# EasyEDA_SCH_Display_2023-01-10.net
KiCad netlist of a schematic drawn in EasyEDA
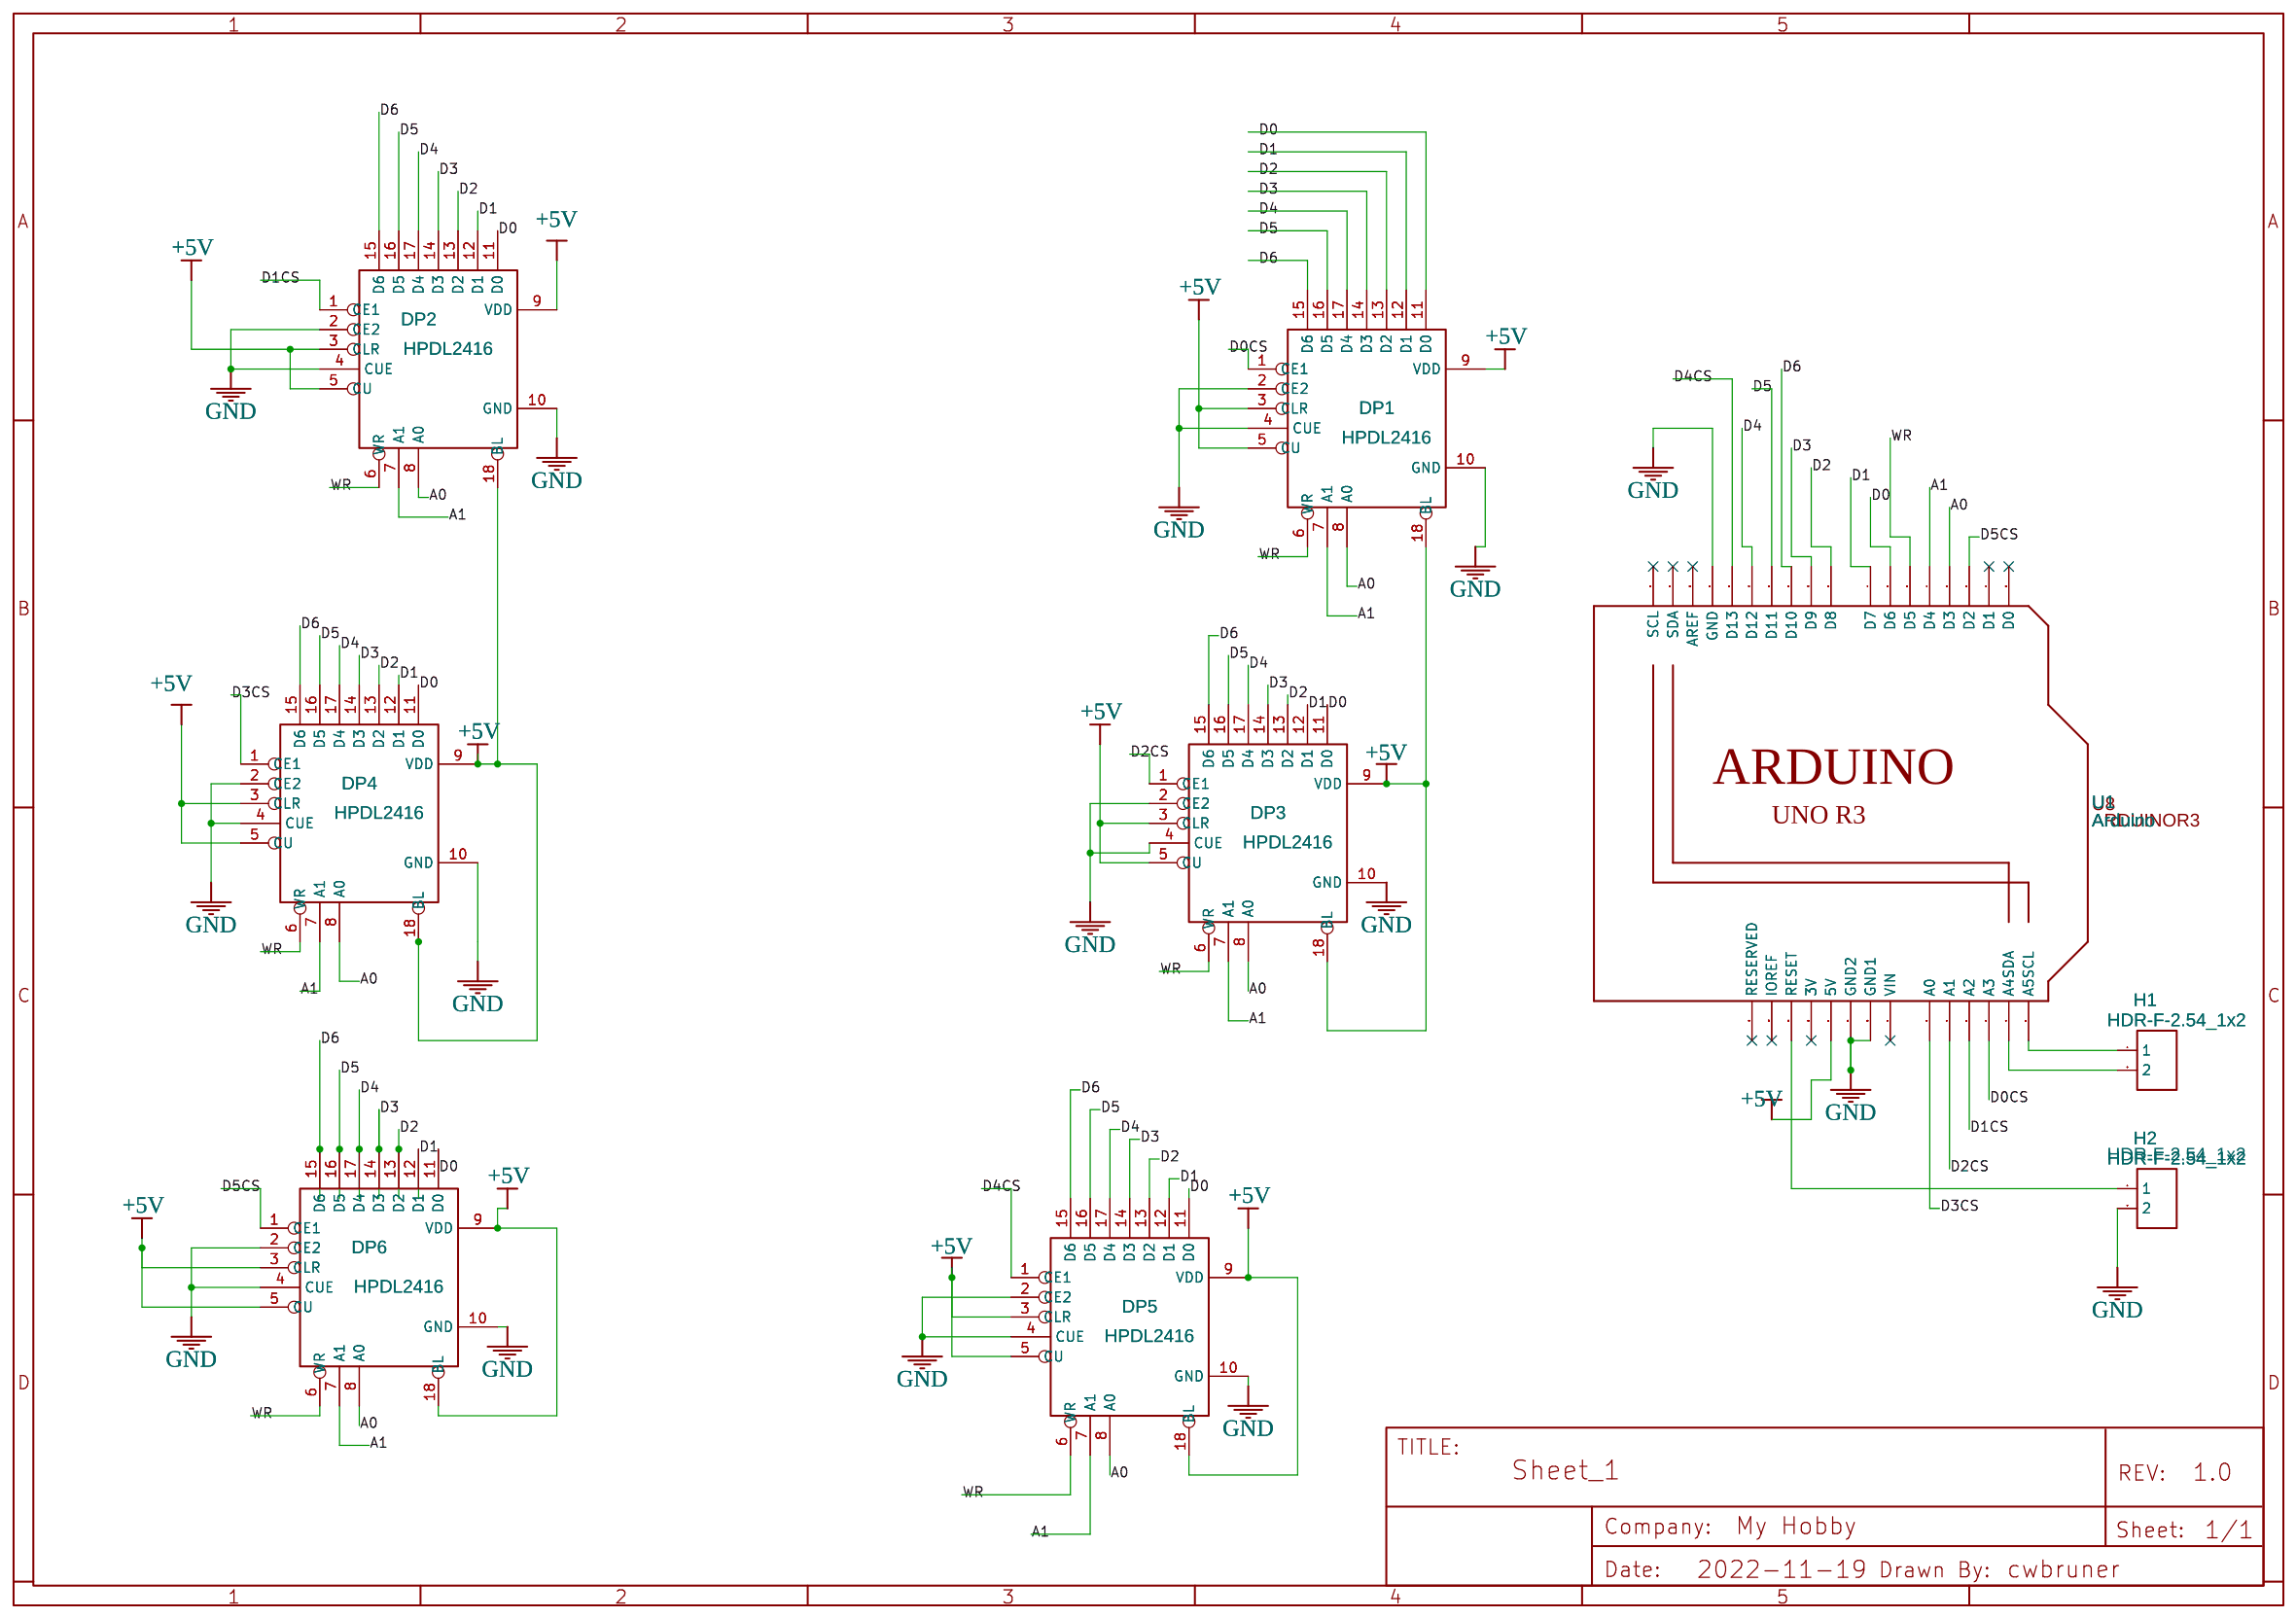
[diagram p0: schematic sheet]

(export (version "E")
  (design (tool "Eeschema 10.0.6"))
  (components
    (comp (ref "DP1")
      (value "HPDL2416")
      (fields (field (name "BOM_Supplier Part") "HPDL-2416"))
      (libsource (lib "") (part "HPDL2416"))
    )
    (comp (ref "DP2")
      (value "HPDL2416")
      (fields (field (name "BOM_Supplier Part") "HPDL-2416"))
      (libsource (lib "") (part "HPDL2416"))
    )
    (comp (ref "DP3")
      (value "HPDL2416")
      (fields (field (name "BOM_Supplier Part") "HPDL-2416"))
      (libsource (lib "") (part "HPDL2416"))
    )
    (comp (ref "DP4")
      (value "HPDL2416")
      (fields (field (name "BOM_Supplier Part") "HPDL-2416"))
      (libsource (lib "") (part "HPDL2416"))
    )
    (comp (ref "DP5")
      (value "HPDL2416")
      (fields (field (name "BOM_Supplier Part") "HPDL-2416"))
      (libsource (lib "") (part "HPDL2416"))
    )
    (comp (ref "DP6")
      (value "HPDL2416")
      (fields (field (name "BOM_Supplier Part") "HPDL-2416"))
      (libsource (lib "") (part "HPDL2416"))
    )
    (comp (ref "H1")
      (value "HDR-F-2.54_1x2")
      (fields (field (name "BOM_Supplier Part") "C49661"))
      (libsource (lib "") (part "HDR-F-2.54_1x2"))
    )
    (comp (ref "H2")
      (value "HDR-F-2.54_1x2")
      (fields (field (name "BOM_Supplier Part") "C49661"))
      (libsource (lib "") (part "HDR-F-2.54_1x2"))
    )
    (comp (ref "U1") (value "Arduino") (libsource (lib "") (part "Arduino")))
  )
  (nets
    (net (code "1") (name "+5V") (class "Default")
      (node (ref "DP1") (pin "18") (pinfunction "BL_18") (pintype "unspecified"))
      (node (ref "DP1") (pin "3") (pinfunction "CLR_3") (pintype "unspecified"))
      (node (ref "DP1") (pin "5") (pinfunction "CU_5") (pintype "unspecified"))
      (node (ref "DP1") (pin "9") (pinfunction "VDD_9") (pintype "unspecified"))
      (node (ref "DP2") (pin "18") (pinfunction "BL_18") (pintype "unspecified"))
      (node (ref "DP2") (pin "3") (pinfunction "CLR_3") (pintype "unspecified"))
      (node (ref "DP2") (pin "5") (pinfunction "CU_5") (pintype "unspecified"))
      (node (ref "DP2") (pin "9") (pinfunction "VDD_9") (pintype "unspecified"))
      (node (ref "DP3") (pin "18") (pinfunction "BL_18") (pintype "unspecified"))
      (node (ref "DP3") (pin "3") (pinfunction "CLR_3") (pintype "unspecified"))
      (node (ref "DP3") (pin "5") (pinfunction "CU_5") (pintype "unspecified"))
      (node (ref "DP3") (pin "9") (pinfunction "VDD_9") (pintype "unspecified"))
      (node (ref "DP4") (pin "18") (pinfunction "BL_18") (pintype "unspecified"))
      (node (ref "DP4") (pin "3") (pinfunction "CLR_3") (pintype "unspecified"))
      (node (ref "DP4") (pin "5") (pinfunction "CU_5") (pintype "unspecified"))
      (node (ref "DP4") (pin "9") (pinfunction "VDD_9") (pintype "unspecified"))
      (node (ref "DP5") (pin "18") (pinfunction "BL_18") (pintype "unspecified"))
      (node (ref "DP5") (pin "3") (pinfunction "CLR_3") (pintype "unspecified"))
      (node (ref "DP5") (pin "5") (pinfunction "CU_5") (pintype "unspecified"))
      (node (ref "DP5") (pin "9") (pinfunction "VDD_9") (pintype "unspecified"))
      (node (ref "DP6") (pin "18") (pinfunction "BL_18") (pintype "unspecified"))
      (node (ref "DP6") (pin "3") (pinfunction "CLR_3") (pintype "unspecified"))
      (node (ref "DP6") (pin "5") (pinfunction "CU_5") (pintype "unspecified"))
      (node (ref "DP6") (pin "9") (pinfunction "VDD_9") (pintype "unspecified"))
      (node (ref "U1") (pin "5V") (pinfunction "5V_5V") (pintype "passive"))
    )
    (net (code "2") (name "/A0") (class "Default")
      (node (ref "DP1") (pin "8") (pinfunction "A0_8") (pintype "unspecified"))
      (node (ref "DP2") (pin "8") (pinfunction "A0_8") (pintype "unspecified"))
      (node (ref "DP3") (pin "8") (pinfunction "A0_8") (pintype "unspecified"))
      (node (ref "DP4") (pin "8") (pinfunction "A0_8") (pintype "unspecified"))
      (node (ref "DP5") (pin "8") (pinfunction "A0_8") (pintype "unspecified"))
      (node (ref "DP6") (pin "8") (pinfunction "A0_8") (pintype "unspecified"))
      (node (ref "U1") (pin "3") (pinfunction "D3_3") (pintype "unspecified"))
    )
    (net (code "3") (name "/A1") (class "Default")
      (node (ref "DP1") (pin "7") (pinfunction "A1_7") (pintype "unspecified"))
      (node (ref "DP2") (pin "7") (pinfunction "A1_7") (pintype "unspecified"))
      (node (ref "DP3") (pin "7") (pinfunction "A1_7") (pintype "unspecified"))
      (node (ref "DP4") (pin "7") (pinfunction "A1_7") (pintype "unspecified"))
      (node (ref "DP5") (pin "7") (pinfunction "A1_7") (pintype "unspecified"))
      (node (ref "DP6") (pin "7") (pinfunction "A1_7") (pintype "unspecified"))
      (node (ref "U1") (pin "4") (pinfunction "D4_4") (pintype "unspecified"))
    )
    (net (code "4") (name "/D0") (class "Default")
      (node (ref "DP1") (pin "11") (pinfunction "D0_11") (pintype "unspecified"))
      (node (ref "DP2") (pin "11") (pinfunction "D0_11") (pintype "unspecified"))
      (node (ref "DP3") (pin "11") (pinfunction "D0_11") (pintype "unspecified"))
      (node (ref "DP4") (pin "11") (pinfunction "D0_11") (pintype "unspecified"))
      (node (ref "DP5") (pin "11") (pinfunction "D0_11") (pintype "unspecified"))
      (node (ref "DP6") (pin "11") (pinfunction "D0_11") (pintype "unspecified"))
      (node (ref "U1") (pin "6") (pinfunction "D6_6") (pintype "unspecified"))
    )
    (net (code "5") (name "/D0CS") (class "Default")
      (node (ref "DP1") (pin "1") (pinfunction "CE1_1") (pintype "unspecified"))
      (node (ref "U1") (pin "A3") (pinfunction "A3_A3") (pintype "unspecified"))
    )
    (net (code "6") (name "/D1") (class "Default")
      (node (ref "DP1") (pin "12") (pinfunction "D1_12") (pintype "unspecified"))
      (node (ref "DP2") (pin "12") (pinfunction "D1_12") (pintype "unspecified"))
      (node (ref "DP3") (pin "12") (pinfunction "D1_12") (pintype "unspecified"))
      (node (ref "DP4") (pin "12") (pinfunction "D1_12") (pintype "unspecified"))
      (node (ref "DP5") (pin "12") (pinfunction "D1_12") (pintype "unspecified"))
      (node (ref "DP6") (pin "12") (pinfunction "D1_12") (pintype "unspecified"))
      (node (ref "U1") (pin "7") (pinfunction "D7_7") (pintype "unspecified"))
    )
    (net (code "7") (name "/D1CS") (class "Default")
      (node (ref "DP2") (pin "1") (pinfunction "CE1_1") (pintype "unspecified"))
      (node (ref "U1") (pin "A2") (pinfunction "A2_A2") (pintype "unspecified"))
    )
    (net (code "8") (name "/D2") (class "Default")
      (node (ref "DP1") (pin "13") (pinfunction "D2_13") (pintype "unspecified"))
      (node (ref "DP2") (pin "13") (pinfunction "D2_13") (pintype "unspecified"))
      (node (ref "DP3") (pin "13") (pinfunction "D2_13") (pintype "unspecified"))
      (node (ref "DP4") (pin "13") (pinfunction "D2_13") (pintype "unspecified"))
      (node (ref "DP5") (pin "13") (pinfunction "D2_13") (pintype "unspecified"))
      (node (ref "DP6") (pin "13") (pinfunction "D2_13") (pintype "unspecified"))
      (node (ref "U1") (pin "8") (pinfunction "D8_8") (pintype "unspecified"))
    )
    (net (code "9") (name "/D2CS") (class "Default")
      (node (ref "DP3") (pin "1") (pinfunction "CE1_1") (pintype "unspecified"))
      (node (ref "U1") (pin "A1") (pinfunction "A1_A1") (pintype "unspecified"))
    )
    (net (code "10") (name "/D3") (class "Default")
      (node (ref "DP1") (pin "14") (pinfunction "D3_14") (pintype "unspecified"))
      (node (ref "DP2") (pin "14") (pinfunction "D3_14") (pintype "unspecified"))
      (node (ref "DP3") (pin "14") (pinfunction "D3_14") (pintype "unspecified"))
      (node (ref "DP4") (pin "14") (pinfunction "D3_14") (pintype "unspecified"))
      (node (ref "DP5") (pin "14") (pinfunction "D3_14") (pintype "unspecified"))
      (node (ref "DP6") (pin "14") (pinfunction "D3_14") (pintype "unspecified"))
      (node (ref "U1") (pin "9") (pinfunction "D9_9") (pintype "unspecified"))
    )
    (net (code "11") (name "/D3CS") (class "Default")
      (node (ref "DP4") (pin "1") (pinfunction "CE1_1") (pintype "unspecified"))
      (node (ref "U1") (pin "A0") (pinfunction "A0_A0") (pintype "unspecified"))
    )
    (net (code "12") (name "/D4") (class "Default")
      (node (ref "DP1") (pin "17") (pinfunction "D4_17") (pintype "unspecified"))
      (node (ref "DP2") (pin "17") (pinfunction "D4_17") (pintype "unspecified"))
      (node (ref "DP3") (pin "17") (pinfunction "D4_17") (pintype "unspecified"))
      (node (ref "DP4") (pin "17") (pinfunction "D4_17") (pintype "unspecified"))
      (node (ref "DP5") (pin "17") (pinfunction "D4_17") (pintype "unspecified"))
      (node (ref "DP6") (pin "17") (pinfunction "D4_17") (pintype "unspecified"))
      (node (ref "U1") (pin "12") (pinfunction "D12_12") (pintype "unspecified"))
    )
    (net (code "13") (name "/D4CS") (class "Default")
      (node (ref "DP5") (pin "1") (pinfunction "CE1_1") (pintype "unspecified"))
      (node (ref "U1") (pin "13") (pinfunction "D13_13") (pintype "unspecified"))
    )
    (net (code "14") (name "/D5") (class "Default")
      (node (ref "DP1") (pin "16") (pinfunction "D5_16") (pintype "unspecified"))
      (node (ref "DP2") (pin "16") (pinfunction "D5_16") (pintype "unspecified"))
      (node (ref "DP3") (pin "16") (pinfunction "D5_16") (pintype "unspecified"))
      (node (ref "DP4") (pin "16") (pinfunction "D5_16") (pintype "unspecified"))
      (node (ref "DP5") (pin "16") (pinfunction "D5_16") (pintype "unspecified"))
      (node (ref "DP6") (pin "16") (pinfunction "D5_16") (pintype "unspecified"))
      (node (ref "U1") (pin "11") (pinfunction "D11_11") (pintype "unspecified"))
    )
    (net (code "15") (name "/D5CS") (class "Default")
      (node (ref "DP6") (pin "1") (pinfunction "CE1_1") (pintype "unspecified"))
      (node (ref "U1") (pin "2") (pinfunction "D2_2") (pintype "unspecified"))
    )
    (net (code "16") (name "/D6") (class "Default")
      (node (ref "DP1") (pin "15") (pinfunction "D6_15") (pintype "unspecified"))
      (node (ref "DP2") (pin "15") (pinfunction "D6_15") (pintype "unspecified"))
      (node (ref "DP3") (pin "15") (pinfunction "D6_15") (pintype "unspecified"))
      (node (ref "DP4") (pin "15") (pinfunction "D6_15") (pintype "unspecified"))
      (node (ref "DP5") (pin "15") (pinfunction "D6_15") (pintype "unspecified"))
      (node (ref "DP6") (pin "15") (pinfunction "D6_15") (pintype "unspecified"))
      (node (ref "U1") (pin "10") (pinfunction "D10_10") (pintype "unspecified"))
    )
    (net (code "17") (name "/WR") (class "Default")
      (node (ref "DP1") (pin "6") (pinfunction "WR_6") (pintype "unspecified"))
      (node (ref "DP2") (pin "6") (pinfunction "WR_6") (pintype "unspecified"))
      (node (ref "DP3") (pin "6") (pinfunction "WR_6") (pintype "unspecified"))
      (node (ref "DP4") (pin "6") (pinfunction "WR_6") (pintype "unspecified"))
      (node (ref "DP5") (pin "6") (pinfunction "WR_6") (pintype "unspecified"))
      (node (ref "DP6") (pin "6") (pinfunction "WR_6") (pintype "unspecified"))
      (node (ref "U1") (pin "5") (pinfunction "D5_5") (pintype "unspecified"))
    )
    (net (code "18") (name "GND") (class "Default")
      (node (ref "DP1") (pin "10") (pinfunction "GND_10") (pintype "unspecified"))
      (node (ref "DP1") (pin "2") (pinfunction "CE2_2") (pintype "unspecified"))
      (node (ref "DP1") (pin "4") (pinfunction "CUE_4") (pintype "unspecified"))
      (node (ref "DP2") (pin "10") (pinfunction "GND_10") (pintype "unspecified"))
      (node (ref "DP2") (pin "2") (pinfunction "CE2_2") (pintype "unspecified"))
      (node (ref "DP2") (pin "4") (pinfunction "CUE_4") (pintype "unspecified"))
      (node (ref "DP3") (pin "10") (pinfunction "GND_10") (pintype "unspecified"))
      (node (ref "DP3") (pin "2") (pinfunction "CE2_2") (pintype "unspecified"))
      (node (ref "DP3") (pin "4") (pinfunction "CUE_4") (pintype "unspecified"))
      (node (ref "DP4") (pin "10") (pinfunction "GND_10") (pintype "unspecified"))
      (node (ref "DP4") (pin "2") (pinfunction "CE2_2") (pintype "unspecified"))
      (node (ref "DP4") (pin "4") (pinfunction "CUE_4") (pintype "unspecified"))
      (node (ref "DP5") (pin "10") (pinfunction "GND_10") (pintype "unspecified"))
      (node (ref "DP5") (pin "2") (pinfunction "CE2_2") (pintype "unspecified"))
      (node (ref "DP5") (pin "4") (pinfunction "CUE_4") (pintype "unspecified"))
      (node (ref "DP6") (pin "10") (pinfunction "GND_10") (pintype "unspecified"))
      (node (ref "DP6") (pin "2") (pinfunction "CE2_2") (pintype "unspecified"))
      (node (ref "DP6") (pin "4") (pinfunction "CUE_4") (pintype "unspecified"))
      (node (ref "H2") (pin "2") (pinfunction "2_2") (pintype "input"))
      (node (ref "U1") (pin "GND") (pinfunction "GND_GND") (pintype "passive"))
    )
    (net (code "19") (name "Net-(H2-Pad1)") (class "Default")
      (node (ref "H2") (pin "1") (pinfunction "1_1") (pintype "input"))
      (node (ref "U1") (pin "RESET") (pinfunction "RESET_RESET") (pintype "unspecified"))
    )
    (net (code "20") (name "Net-(U1-A4SDA)") (class "Default")
      (node (ref "H1") (pin "2") (pinfunction "2_2") (pintype "input"))
      (node (ref "U1") (pin "A4") (pinfunction "A4SDA_A4") (pintype "unspecified"))
    )
    (net (code "21") (name "Net-(U1-A5SCL)") (class "Default")
      (node (ref "H1") (pin "1") (pinfunction "1_1") (pintype "input"))
      (node (ref "U1") (pin "A5") (pinfunction "A5SCL_A5") (pintype "unspecified"))
    )
    (net (code "22") (name "unconnected-(U1-3V-Pad3.3V)") (class "Default")
      (node (ref "U1") (pin "3.3V") (pinfunction "3V_3.3V") (pintype "passive+no_connect"))
    )
    (net (code "23") (name "unconnected-(U1-D0-Pad0)") (class "Default")
      (node (ref "U1") (pin "0") (pinfunction "D0_0") (pintype "unspecified+no_connect"))
    )
    (net (code "24") (name "unconnected-(U1-D1-Pad1)") (class "Default")
      (node (ref "U1") (pin "1") (pinfunction "D1_1") (pintype "unspecified+no_connect"))
    )
    (net (code "25") (name "unconnected-(U1-IOREF-PadI{slash}OREF)") (class "Default")
      (node (ref "U1") (pin "I/OREF") (pinfunction "IOREF_I/OREF") (pintype "output+no_connect"))
    )
    (net (code "26") (name "unconnected-(U1-PadAREF)") (class "Default")
      (node (ref "U1") (pin "AREF") (pinfunction "AREF_AREF") (pintype "unspecified+no_connect"))
    )
    (net (code "27") (name "unconnected-(U1-PadSCL)") (class "Default")
      (node (ref "U1") (pin "SCL") (pinfunction "SCL_SCL") (pintype "unspecified+no_connect"))
    )
    (net (code "28") (name "unconnected-(U1-PadSDA)") (class "Default")
      (node (ref "U1") (pin "SDA") (pinfunction "SDA_SDA") (pintype "unspecified+no_connect"))
    )
    (net (code "29") (name "unconnected-(U1-PadVIN)") (class "Default")
      (node (ref "U1") (pin "VIN") (pinfunction "VIN_VIN") (pintype "passive+no_connect"))
    )
    (net (code "30") (name "unconnected-(U1-RESERVED-PadN{slash}C)") (class "Default")
      (node (ref "U1") (pin "N/C") (pinfunction "RESERVED_N/C") (pintype "unspecified+no_connect"))
    )
  )
)
